# penny.net
KiCad netlist of a schematic drawn in EAGLE
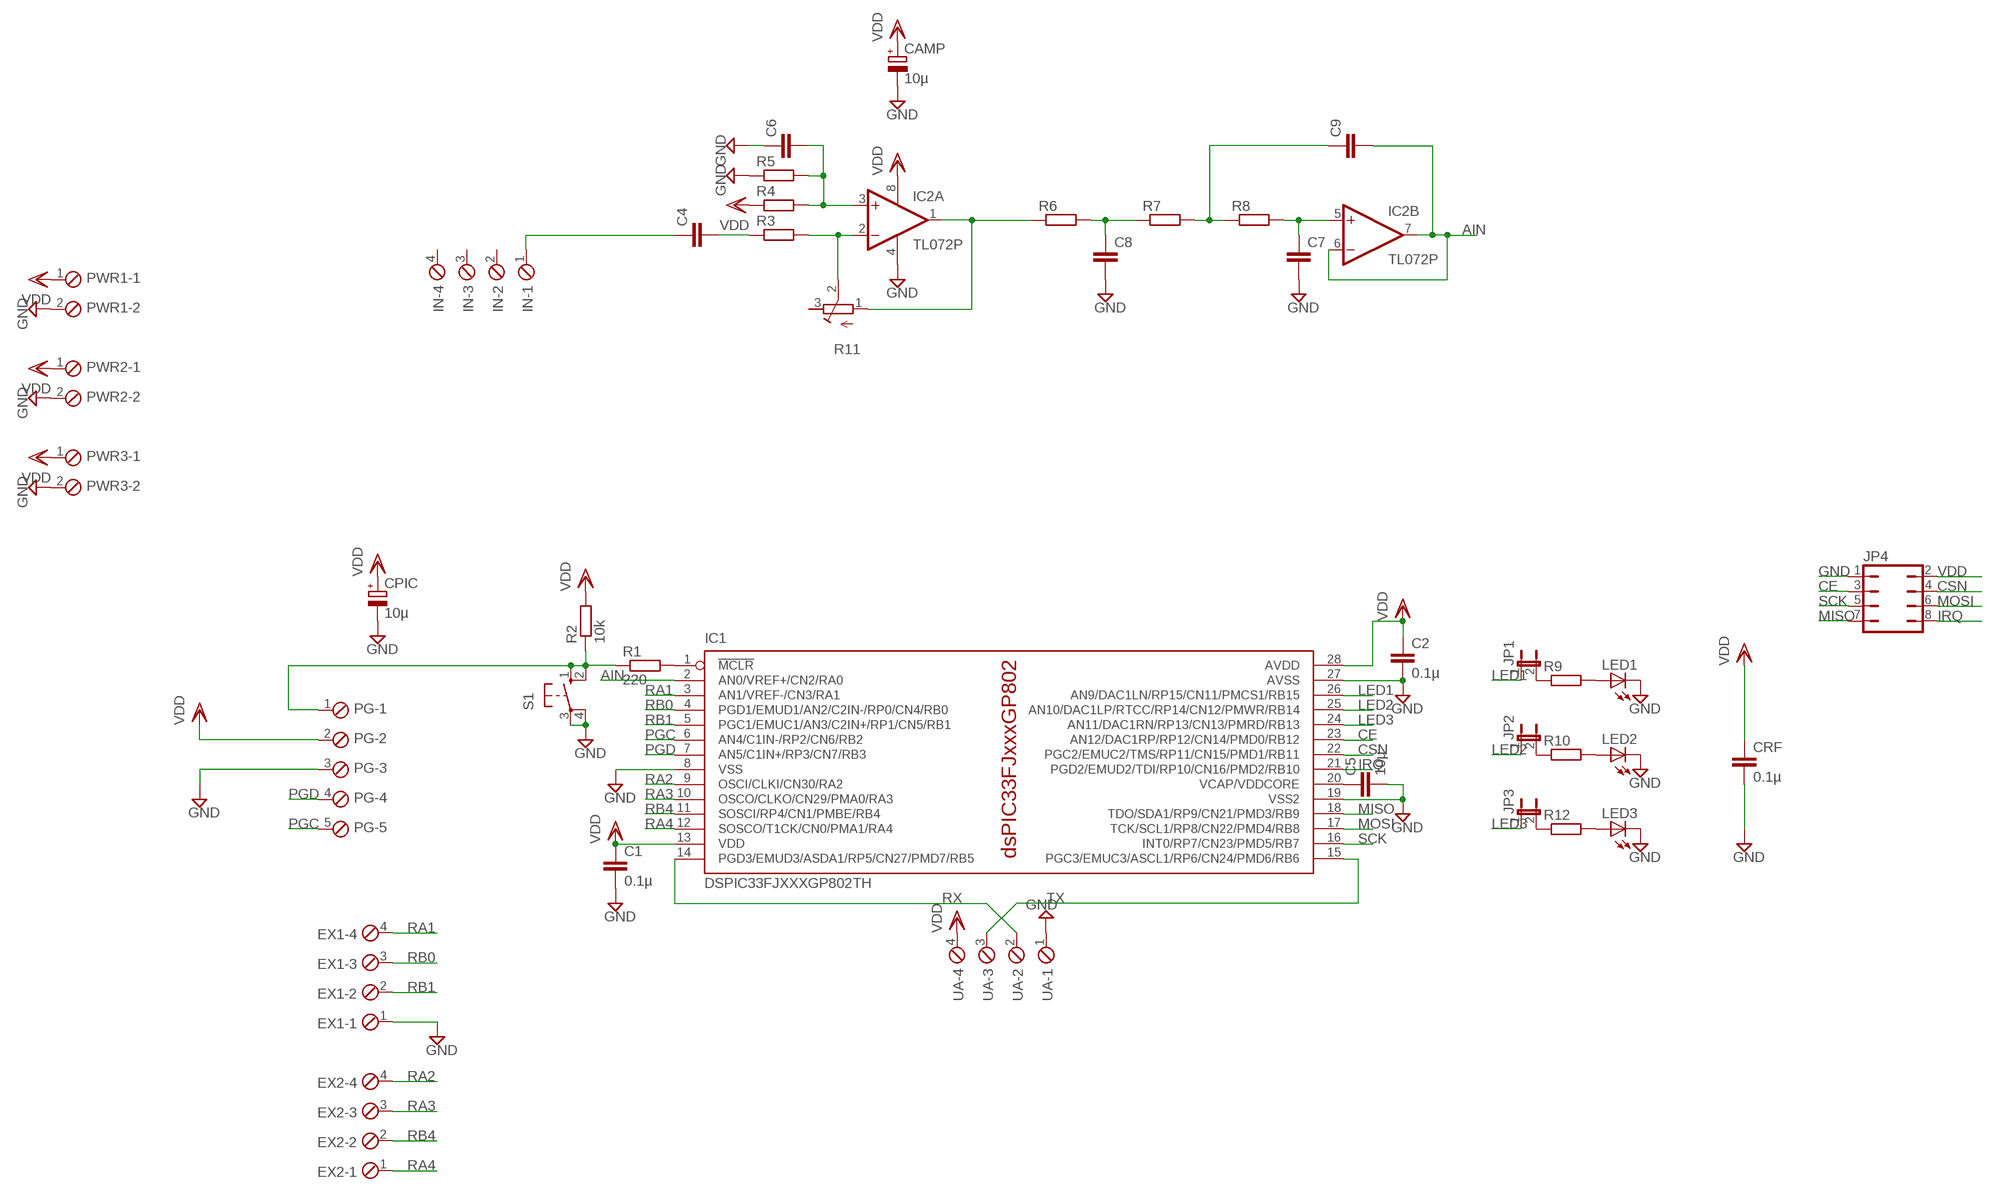
[diagram p0: schematic, sheet 1]

(export (version "E")
  (design (tool "Eeschema 10.0.6"))
  (components
    (comp (ref "C1")
      (value "0.1µ")
      (footprint "eagle-import:C025-024X044")
      (libsource (lib "eagle-import") (part "C-EU025-024X044"))
    )
    (comp (ref "C2")
      (value "0.1µ")
      (footprint "eagle-import:C025-024X044")
      (libsource (lib "eagle-import") (part "C-EU025-024X044"))
    )
    (comp (ref "C4")
      (value "C-EU025-024X044")
      (footprint "eagle-import:C025-024X044")
      (libsource (lib "eagle-import") (part "C-EU025-024X044"))
    )
    (comp (ref "C5")
      (value "10µ")
      (footprint "eagle-import:C025-024X044")
      (libsource (lib "eagle-import") (part "C-EU025-024X044"))
    )
    (comp (ref "C6")
      (value "C-EU025-024X044")
      (footprint "eagle-import:C025-024X044")
      (libsource (lib "eagle-import") (part "C-EU025-024X044"))
    )
    (comp (ref "C7")
      (value "C-EU025-024X044")
      (footprint "eagle-import:C025-024X044")
      (libsource (lib "eagle-import") (part "C-EU025-024X044"))
    )
    (comp (ref "C8")
      (value "C-EU025-024X044")
      (footprint "eagle-import:C025-024X044")
      (libsource (lib "eagle-import") (part "C-EU025-024X044"))
    )
    (comp (ref "C9")
      (value "C-EU025-024X044")
      (footprint "eagle-import:C025-024X044")
      (libsource (lib "eagle-import") (part "C-EU025-024X044"))
    )
    (comp (ref "CAMP")
      (value "10µ")
      (footprint "eagle-import:E2,5-5")
      (libsource (lib "eagle-import") (part "CPOL-EUE2.5-5"))
    )
    (comp (ref "CPIC")
      (value "10µ")
      (footprint "eagle-import:E2,5-5")
      (libsource (lib "eagle-import") (part "CPOL-EUE2.5-5"))
    )
    (comp (ref "CRF")
      (value "0.1µ")
      (footprint "eagle-import:C025-024X044")
      (libsource (lib "eagle-import") (part "C-EU025-024X044"))
    )
    (comp (ref "EX1")
      (value "MPT4")
      (footprint "eagle-import:4POL254")
      (libsource (lib "eagle-import") (part "MPT4"))
    )
    (comp (ref "EX2")
      (value "MPT4")
      (footprint "eagle-import:4POL254")
      (libsource (lib "eagle-import") (part "MPT4"))
    )
    (comp (ref "IC1")
      (value "DSPIC33FJXXXGP802TH")
      (footprint "eagle-import:DIL28-3")
      (libsource (lib "eagle-import") (part "DSPIC33FJXXXGP802TH"))
    )
    (comp (ref "IC2")
      (value "TL072P")
      (footprint "eagle-import:DIL08")
      (libsource (lib "eagle-import") (part "TL072P"))
    )
    (comp (ref "IN")
      (value "MPT4")
      (footprint "eagle-import:4POL254")
      (libsource (lib "eagle-import") (part "MPT4"))
    )
    (comp (ref "JP1")
      (value "JP1E")
      (footprint "eagle-import:JP1")
      (libsource (lib "eagle-import") (part "JP1E"))
    )
    (comp (ref "JP2")
      (value "JP1E")
      (footprint "eagle-import:JP1")
      (libsource (lib "eagle-import") (part "JP1E"))
    )
    (comp (ref "JP3")
      (value "JP1E")
      (footprint "eagle-import:JP1")
      (libsource (lib "eagle-import") (part "JP1E"))
    )
    (comp (ref "JP4")
      (value "JP4Q")
      (footprint "eagle-import:JP4Q")
      (libsource (lib "eagle-import") (part "JP4Q"))
    )
    (comp (ref "LED1")
      (value "LED3MM")
      (footprint "eagle-import:LED3MM")
      (libsource (lib "eagle-import") (part "LED3MM"))
    )
    (comp (ref "LED2")
      (value "LED3MM")
      (footprint "eagle-import:LED3MM")
      (libsource (lib "eagle-import") (part "LED3MM"))
    )
    (comp (ref "LED3")
      (value "LED3MM")
      (footprint "eagle-import:LED3MM")
      (libsource (lib "eagle-import") (part "LED3MM"))
    )
    (comp (ref "PG")
      (value "MPT5")
      (footprint "eagle-import:5POL254")
      (libsource (lib "eagle-import") (part "MPT5"))
    )
    (comp (ref "PWR1")
      (value "MPT2")
      (footprint "eagle-import:2POL254")
      (libsource (lib "eagle-import") (part "MPT2"))
    )
    (comp (ref "PWR2")
      (value "MPT2")
      (footprint "eagle-import:2POL254")
      (libsource (lib "eagle-import") (part "MPT2"))
    )
    (comp (ref "PWR3")
      (value "MPT2")
      (footprint "eagle-import:2POL254")
      (libsource (lib "eagle-import") (part "MPT2"))
    )
    (comp (ref "R1")
      (value "220")
      (footprint "eagle-import:0207_10")
      (libsource (lib "eagle-import") (part "R-EU_0207/10"))
    )
    (comp (ref "R2")
      (value "10k")
      (footprint "eagle-import:0207_10")
      (libsource (lib "eagle-import") (part "R-EU_0207/10"))
    )
    (comp (ref "R3")
      (value "R-EU_0207/10")
      (footprint "eagle-import:0207_10")
      (libsource (lib "eagle-import") (part "R-EU_0207/10"))
    )
    (comp (ref "R4")
      (value "R-EU_0207/10")
      (footprint "eagle-import:0207_10")
      (libsource (lib "eagle-import") (part "R-EU_0207/10"))
    )
    (comp (ref "R5")
      (value "R-EU_0207/10")
      (footprint "eagle-import:0207_10")
      (libsource (lib "eagle-import") (part "R-EU_0207/10"))
    )
    (comp (ref "R6")
      (value "R-EU_0207/10")
      (footprint "eagle-import:0207_10")
      (libsource (lib "eagle-import") (part "R-EU_0207/10"))
    )
    (comp (ref "R7")
      (value "R-EU_0207/10")
      (footprint "eagle-import:0207_10")
      (libsource (lib "eagle-import") (part "R-EU_0207/10"))
    )
    (comp (ref "R8")
      (value "R-EU_0207/10")
      (footprint "eagle-import:0207_10")
      (libsource (lib "eagle-import") (part "R-EU_0207/10"))
    )
    (comp (ref "R9")
      (value "R-EU_0207/10")
      (footprint "eagle-import:0207_10")
      (libsource (lib "eagle-import") (part "R-EU_0207/10"))
    )
    (comp (ref "R10")
      (value "R-EU_0207/10")
      (footprint "eagle-import:0207_10")
      (libsource (lib "eagle-import") (part "R-EU_0207/10"))
    )
    (comp (ref "R11")
      (value "R-TRIMM3339P")
      (footprint "eagle-import:RTRIM3339P")
      (libsource (lib "eagle-import") (part "R-TRIMM3339P"))
    )
    (comp (ref "R12")
      (value "R-EU_0207/10")
      (footprint "eagle-import:0207_10")
      (libsource (lib "eagle-import") (part "R-EU_0207/10"))
    )
    (comp (ref "S1")
      (value "10-XX")
      (footprint "eagle-import:B3F-10XX")
      (fields (field (name "MPN") "B3F-1000"))
      (libsource (lib "eagle-import") (part "10-XX"))
    )
    (comp (ref "UA")
      (value "MPT4")
      (footprint "eagle-import:4POL254")
      (libsource (lib "eagle-import") (part "MPT4"))
    )
  )
  (nets
    (net (code "1") (name "/AIN") (class "Default")
      (node (ref "C9") (pin "2") (pinfunction "2_2") (pintype "passive"))
      (node (ref "IC1") (pin "2") (pinfunction "AN0/VREF+/CN2/RA0_2") (pintype "bidirectional"))
      (node (ref "IC2") (pin "6") (pinfunction "-IN_6") (pintype "input"))
      (node (ref "IC2") (pin "7") (pinfunction "OUT_7") (pintype "output"))
    )
    (net (code "2") (name "/CE") (class "Default")
      (node (ref "IC1") (pin "23") (pinfunction "AN12/DAC1RP/RP12/CN14/PMD0/RB12_23") (pintype "bidirectional"))
      (node (ref "JP4") (pin "3") (pinfunction "3_3") (pintype "passive"))
    )
    (net (code "3") (name "/CSN") (class "Default")
      (node (ref "IC1") (pin "22") (pinfunction "PGC2/EMUC2/TMS/RP11/CN15/PMD1/RB11_22") (pintype "bidirectional"))
      (node (ref "JP4") (pin "4") (pinfunction "4_4") (pintype "passive"))
    )
    (net (code "4") (name "/IRQ") (class "Default")
      (node (ref "IC1") (pin "21") (pinfunction "PGD2/EMUD2/TDI/RP10/CN16/PMD2/RB10_21") (pintype "bidirectional"))
      (node (ref "JP4") (pin "8") (pinfunction "8_8") (pintype "passive"))
    )
    (net (code "5") (name "/LED1") (class "Default")
      (node (ref "IC1") (pin "26") (pinfunction "AN9/DAC1LN/RP15/CN11/PMCS1/RB15_26") (pintype "bidirectional"))
      (node (ref "JP1") (pin "1") (pinfunction "1_1") (pintype "passive"))
    )
    (net (code "6") (name "/LED2") (class "Default")
      (node (ref "IC1") (pin "25") (pinfunction "AN10/DAC1LP/RTCC/RP14/CN12/PMWR/RB14_25") (pintype "bidirectional"))
      (node (ref "JP2") (pin "1") (pinfunction "1_1") (pintype "passive"))
    )
    (net (code "7") (name "/LED3") (class "Default")
      (node (ref "IC1") (pin "24") (pinfunction "AN11/DAC1RN/RP13/CN13/PMRD/RB13_24") (pintype "bidirectional"))
      (node (ref "JP3") (pin "1") (pinfunction "1_1") (pintype "passive"))
    )
    (net (code "8") (name "/MISO") (class "Default")
      (node (ref "IC1") (pin "18") (pinfunction "TDO/SDA1/RP9/CN21/PMD3/RB9_18") (pintype "bidirectional"))
      (node (ref "JP4") (pin "7") (pinfunction "7_7") (pintype "passive"))
    )
    (net (code "9") (name "/MOSI") (class "Default")
      (node (ref "IC1") (pin "17") (pinfunction "TCK/SCL1/RP8/CN22/PMD4/RB8_17") (pintype "bidirectional"))
      (node (ref "JP4") (pin "6") (pinfunction "6_6") (pintype "passive"))
    )
    (net (code "10") (name "/PGC") (class "Default")
      (node (ref "IC1") (pin "6") (pinfunction "AN4/C1IN-/RP2/CN6/RB2_6") (pintype "bidirectional"))
      (node (ref "PG") (pin "5") (pinfunction "1_5") (pintype "passive"))
    )
    (net (code "11") (name "/PGD") (class "Default")
      (node (ref "IC1") (pin "7") (pinfunction "AN5/C1IN+/RP3/CN7/RB3_7") (pintype "bidirectional"))
      (node (ref "PG") (pin "4") (pinfunction "1_4") (pintype "passive"))
    )
    (net (code "12") (name "/RA1") (class "Default")
      (node (ref "EX1") (pin "4") (pinfunction "1_4") (pintype "passive"))
      (node (ref "IC1") (pin "3") (pinfunction "AN1/VREF-/CN3/RA1_3") (pintype "bidirectional"))
    )
    (net (code "13") (name "/RA2") (class "Default")
      (node (ref "EX2") (pin "4") (pinfunction "1_4") (pintype "passive"))
      (node (ref "IC1") (pin "9") (pinfunction "OSCI/CLKI/CN30/RA2_9") (pintype "bidirectional"))
    )
    (net (code "14") (name "/RA3") (class "Default")
      (node (ref "EX2") (pin "3") (pinfunction "1_3") (pintype "passive"))
      (node (ref "IC1") (pin "10") (pinfunction "OSCO/CLKO/CN29/PMA0/RA3_10") (pintype "bidirectional"))
    )
    (net (code "15") (name "/RA4") (class "Default")
      (node (ref "EX2") (pin "1") (pinfunction "1_1") (pintype "passive"))
      (node (ref "IC1") (pin "12") (pinfunction "SOSCO/T1CK/CN0/PMA1/RA4_12") (pintype "bidirectional"))
    )
    (net (code "16") (name "/RB0") (class "Default")
      (node (ref "EX1") (pin "3") (pinfunction "1_3") (pintype "passive"))
      (node (ref "IC1") (pin "4") (pinfunction "PGD1/EMUD1/AN2/C2IN-/RP0/CN4/RB0_4") (pintype "bidirectional"))
    )
    (net (code "17") (name "/RB1") (class "Default")
      (node (ref "EX1") (pin "2") (pinfunction "1_2") (pintype "passive"))
      (node (ref "IC1") (pin "5") (pinfunction "PGC1/EMUC1/AN3/C2IN+/RP1/CN5/RB1_5") (pintype "bidirectional"))
    )
    (net (code "18") (name "/RB4") (class "Default")
      (node (ref "EX2") (pin "2") (pinfunction "1_2") (pintype "passive"))
      (node (ref "IC1") (pin "11") (pinfunction "SOSCI/RP4/CN1/PMBE/RB4_11") (pintype "bidirectional"))
    )
    (net (code "19") (name "/RX") (class "Default")
      (node (ref "IC1") (pin "14") (pinfunction "PGD3/EMUD3/ASDA1/RP5/CN27/PMD7/RB5_14") (pintype "bidirectional"))
      (node (ref "UA") (pin "2") (pinfunction "1_2") (pintype "passive"))
    )
    (net (code "20") (name "/SCK") (class "Default")
      (node (ref "IC1") (pin "16") (pinfunction "INT0/RP7/CN23/PMD5/RB7_16") (pintype "bidirectional"))
      (node (ref "JP4") (pin "5") (pinfunction "5_5") (pintype "passive"))
    )
    (net (code "21") (name "/TX") (class "Default")
      (node (ref "IC1") (pin "15") (pinfunction "PGC3/EMUC3/ASCL1/RP6/CN24/PMD6/RB6_15") (pintype "bidirectional"))
      (node (ref "UA") (pin "3") (pinfunction "1_3") (pintype "passive"))
    )
    (net (code "22") (name "GND") (class "Default")
      (node (ref "C1") (pin "2") (pinfunction "2_2") (pintype "passive"))
      (node (ref "C2") (pin "2") (pinfunction "2_2") (pintype "passive"))
      (node (ref "C5") (pin "2") (pinfunction "2_2") (pintype "passive"))
      (node (ref "C6") (pin "1") (pinfunction "1_1") (pintype "passive"))
      (node (ref "C7") (pin "2") (pinfunction "2_2") (pintype "passive"))
      (node (ref "C8") (pin "2") (pinfunction "2_2") (pintype "passive"))
      (node (ref "CAMP") (pin "-") (pinfunction "-_-") (pintype "passive"))
      (node (ref "CPIC") (pin "-") (pinfunction "-_-") (pintype "passive"))
      (node (ref "CRF") (pin "2") (pinfunction "2_2") (pintype "passive"))
      (node (ref "EX1") (pin "1") (pinfunction "1_1") (pintype "passive"))
      (node (ref "IC1") (pin "19") (pinfunction "VSS2_19") (pintype "power_in"))
      (node (ref "IC1") (pin "27") (pinfunction "AVSS_27") (pintype "power_in"))
      (node (ref "IC1") (pin "8") (pinfunction "VSS_8") (pintype "power_in"))
      (node (ref "IC2") (pin "4") (pinfunction "V-_4") (pintype "power_in"))
      (node (ref "JP4") (pin "1") (pinfunction "1_1") (pintype "passive"))
      (node (ref "LED1") (pin "K") (pinfunction "C_K") (pintype "passive"))
      (node (ref "LED2") (pin "K") (pinfunction "C_K") (pintype "passive"))
      (node (ref "LED3") (pin "K") (pinfunction "C_K") (pintype "passive"))
      (node (ref "PG") (pin "3") (pinfunction "1_3") (pintype "passive"))
      (node (ref "PWR1") (pin "2") (pinfunction "1_2") (pintype "passive"))
      (node (ref "PWR2") (pin "2") (pinfunction "1_2") (pintype "passive"))
      (node (ref "PWR3") (pin "2") (pinfunction "1_2") (pintype "passive"))
      (node (ref "R5") (pin "1") (pinfunction "1_1") (pintype "passive"))
      (node (ref "S1") (pin "3") (pinfunction "P_3") (pintype "passive"))
      (node (ref "S1") (pin "4") (pinfunction "P1_4") (pintype "passive"))
      (node (ref "UA") (pin "1") (pinfunction "1_1") (pintype "passive"))
    )
    (net (code "23") (name "Net-(C4-Pad1)") (class "Default")
      (node (ref "C4") (pin "1") (pinfunction "1_1") (pintype "passive"))
      (node (ref "IN") (pin "1") (pinfunction "1_1") (pintype "passive"))
    )
    (net (code "24") (name "Net-(C4-Pad2)") (class "Default")
      (node (ref "C4") (pin "2") (pinfunction "2_2") (pintype "passive"))
      (node (ref "R3") (pin "1") (pinfunction "1_1") (pintype "passive"))
    )
    (net (code "25") (name "Net-(C8-Pad1)") (class "Default")
      (node (ref "C8") (pin "1") (pinfunction "1_1") (pintype "passive"))
      (node (ref "R6") (pin "2") (pinfunction "2_2") (pintype "passive"))
      (node (ref "R7") (pin "1") (pinfunction "1_1") (pintype "passive"))
    )
    (net (code "26") (name "Net-(C9-Pad1)") (class "Default")
      (node (ref "C9") (pin "1") (pinfunction "1_1") (pintype "passive"))
      (node (ref "R7") (pin "2") (pinfunction "2_2") (pintype "passive"))
      (node (ref "R8") (pin "1") (pinfunction "1_1") (pintype "passive"))
    )
    (net (code "27") (name "Net-(IC1-VCAP{slash}VDDCORE)") (class "Default")
      (node (ref "C5") (pin "1") (pinfunction "1_1") (pintype "passive"))
      (node (ref "IC1") (pin "20") (pinfunction "VCAP/VDDCORE_20") (pintype "power_in"))
    )
    (net (code "28") (name "Net-(IC1-~{MCLR})") (class "Default")
      (node (ref "IC1") (pin "1") (pinfunction "~{MCLR}_1") (pintype "input"))
      (node (ref "R1") (pin "2") (pinfunction "2_2") (pintype "passive"))
    )
    (net (code "29") (name "Net-(IC2A-+IN)") (class "Default")
      (node (ref "C6") (pin "2") (pinfunction "2_2") (pintype "passive"))
      (node (ref "IC2") (pin "3") (pinfunction "+IN_3") (pintype "input"))
      (node (ref "R4") (pin "2") (pinfunction "2_2") (pintype "passive"))
      (node (ref "R5") (pin "2") (pinfunction "2_2") (pintype "passive"))
    )
    (net (code "30") (name "Net-(IC2A--IN)") (class "Default")
      (node (ref "IC2") (pin "2") (pinfunction "-IN_2") (pintype "input"))
      (node (ref "R11") (pin "2") (pinfunction "S_2") (pintype "passive"))
      (node (ref "R3") (pin "2") (pinfunction "2_2") (pintype "passive"))
    )
    (net (code "31") (name "Net-(IC2A-OUT)") (class "Default")
      (node (ref "IC2") (pin "1") (pinfunction "OUT_1") (pintype "output"))
      (node (ref "R11") (pin "1") (pinfunction "A_1") (pintype "passive"))
      (node (ref "R6") (pin "1") (pinfunction "1_1") (pintype "passive"))
    )
    (net (code "32") (name "Net-(IC2B-+IN)") (class "Default")
      (node (ref "C7") (pin "1") (pinfunction "1_1") (pintype "passive"))
      (node (ref "IC2") (pin "5") (pinfunction "+IN_5") (pintype "input"))
      (node (ref "R8") (pin "2") (pinfunction "2_2") (pintype "passive"))
    )
    (net (code "33") (name "Net-(JP1-Pad2)") (class "Default")
      (node (ref "JP1") (pin "2") (pinfunction "2_2") (pintype "passive"))
      (node (ref "R9") (pin "1") (pinfunction "1_1") (pintype "passive"))
    )
    (net (code "34") (name "Net-(JP2-Pad2)") (class "Default")
      (node (ref "JP2") (pin "2") (pinfunction "2_2") (pintype "passive"))
      (node (ref "R10") (pin "1") (pinfunction "1_1") (pintype "passive"))
    )
    (net (code "35") (name "Net-(JP3-Pad2)") (class "Default")
      (node (ref "JP3") (pin "2") (pinfunction "2_2") (pintype "passive"))
      (node (ref "R12") (pin "1") (pinfunction "1_1") (pintype "passive"))
    )
    (net (code "36") (name "Net-(LED1-PadA)") (class "Default")
      (node (ref "LED1") (pin "A") (pinfunction "A_A") (pintype "passive"))
      (node (ref "R9") (pin "2") (pinfunction "2_2") (pintype "passive"))
    )
    (net (code "37") (name "Net-(LED2-PadA)") (class "Default")
      (node (ref "LED2") (pin "A") (pinfunction "A_A") (pintype "passive"))
      (node (ref "R10") (pin "2") (pinfunction "2_2") (pintype "passive"))
    )
    (net (code "38") (name "Net-(LED3-PadA)") (class "Default")
      (node (ref "LED3") (pin "A") (pinfunction "A_A") (pintype "passive"))
      (node (ref "R12") (pin "2") (pinfunction "2_2") (pintype "passive"))
    )
    (net (code "39") (name "Net-(S1-S)") (class "Default")
      (node (ref "PG") (pin "1") (pinfunction "1_1") (pintype "passive"))
      (node (ref "R1") (pin "1") (pinfunction "1_1") (pintype "passive"))
      (node (ref "R2") (pin "1") (pinfunction "1_1") (pintype "passive"))
      (node (ref "S1") (pin "1") (pinfunction "S_1") (pintype "passive"))
      (node (ref "S1") (pin "2") (pinfunction "S1_2") (pintype "passive"))
    )
    (net (code "40") (name "VDD") (class "Default")
      (node (ref "C1") (pin "1") (pinfunction "1_1") (pintype "passive"))
      (node (ref "C2") (pin "1") (pinfunction "1_1") (pintype "passive"))
      (node (ref "CAMP") (pin "+") (pinfunction "+_+") (pintype "passive"))
      (node (ref "CPIC") (pin "+") (pinfunction "+_+") (pintype "passive"))
      (node (ref "CRF") (pin "1") (pinfunction "1_1") (pintype "passive"))
      (node (ref "IC1") (pin "13") (pinfunction "VDD_13") (pintype "power_in"))
      (node (ref "IC1") (pin "28") (pinfunction "AVDD_28") (pintype "power_in"))
      (node (ref "IC2") (pin "8") (pinfunction "V+_8") (pintype "power_in"))
      (node (ref "JP4") (pin "2") (pinfunction "2_2") (pintype "passive"))
      (node (ref "PG") (pin "2") (pinfunction "1_2") (pintype "passive"))
      (node (ref "PWR1") (pin "1") (pinfunction "1_1") (pintype "passive"))
      (node (ref "PWR2") (pin "1") (pinfunction "1_1") (pintype "passive"))
      (node (ref "PWR3") (pin "1") (pinfunction "1_1") (pintype "passive"))
      (node (ref "R2") (pin "2") (pinfunction "2_2") (pintype "passive"))
      (node (ref "R4") (pin "1") (pinfunction "1_1") (pintype "passive"))
      (node (ref "UA") (pin "4") (pinfunction "1_4") (pintype "passive"))
    )
    (net (code "41") (name "unconnected-(INB-1-Pad2)") (class "Default")
      (node (ref "IN") (pin "2") (pinfunction "1_2") (pintype "passive"))
    )
    (net (code "42") (name "unconnected-(INC-1-Pad3)") (class "Default")
      (node (ref "IN") (pin "3") (pinfunction "1_3") (pintype "passive"))
    )
    (net (code "43") (name "unconnected-(IND-1-Pad4)") (class "Default")
      (node (ref "IN") (pin "4") (pinfunction "1_4") (pintype "passive"))
    )
    (net (code "44") (name "unconnected-(R11-E-Pad3)") (class "Default")
      (node (ref "R11") (pin "3") (pinfunction "E_3") (pintype "passive"))
    )
  )
)
